# FRAM-DIP.net
KiCad netlist of a schematic drawn in EAGLE
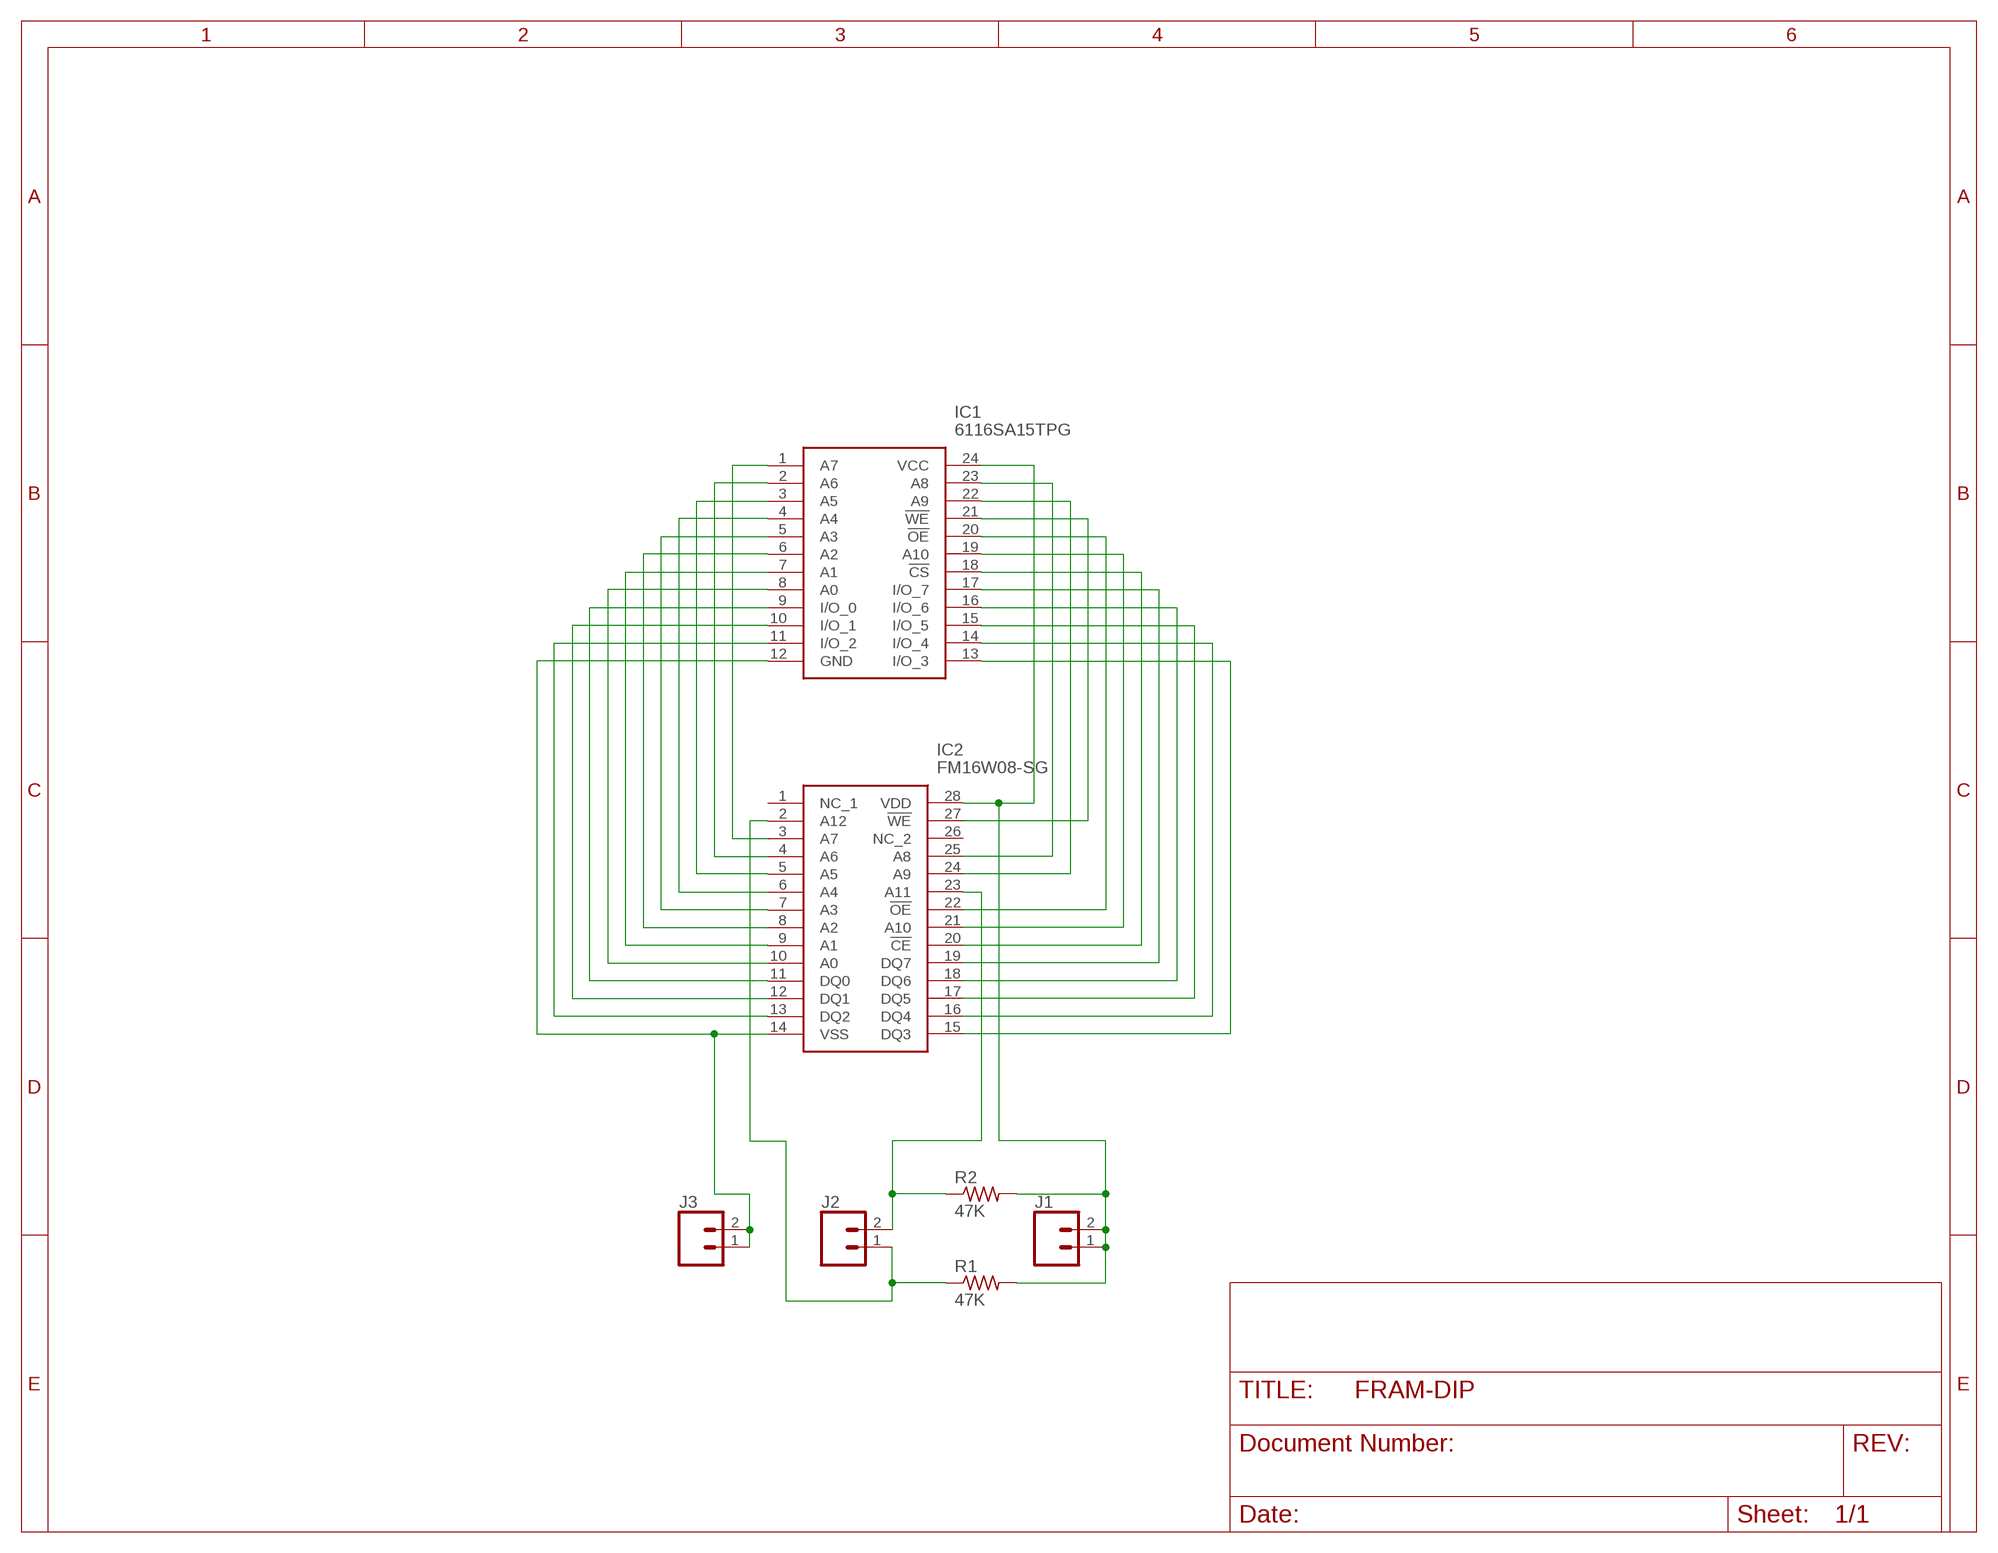
[diagram p0: schematic, sheet 1]

(export (version "E")
  (design (tool "Eeschema 10.0.6"))
  (components
    (comp (ref "IC1")
      (value "6116SA15TPG")
      (footprint "eagle-import:DIP864W51P254L3169H381Q24N")
      (fields (field (name "MOUSER_PART_NUMBER") "972-6116SA15TPG"))
      (libsource (lib "eagle-import") (part "6116SA15TPG"))
    )
    (comp (ref "IC2")
      (value "FM16W08-SG")
      (footprint "eagle-import:SOIC127P1032X267-28N")
      (fields (field (name "MOUSER_PART_NUMBER") "877-FM16W08-SG"))
      (libsource (lib "eagle-import") (part "FM16W08-SG"))
    )
    (comp (ref "J1")
      (value "CONN_02")
      (footprint "eagle-import:1X02")
      (libsource (lib "eagle-import") (part "CONN_02"))
    )
    (comp (ref "J2")
      (value "CONN_02")
      (footprint "eagle-import:1X02")
      (libsource (lib "eagle-import") (part "CONN_02"))
    )
    (comp (ref "J3")
      (value "CONN_02")
      (footprint "eagle-import:1X02")
      (libsource (lib "eagle-import") (part "CONN_02"))
    )
    (comp (ref "R1")
      (value "47K")
      (footprint "eagle-import:R0805")
      (libsource (lib "eagle-import") (part "R-US_R0805"))
    )
    (comp (ref "R2")
      (value "47K")
      (footprint "eagle-import:R0805")
      (libsource (lib "eagle-import") (part "R-US_R0805"))
    )
  )
  (nets
    (net (code "1") (name "Net-(IC1-A0)") (class "Default")
      (node (ref "IC1") (pin "8") (pinfunction "A0_8") (pintype "bidirectional"))
      (node (ref "IC2") (pin "10") (pinfunction "A0_10") (pintype "input"))
    )
    (net (code "2") (name "Net-(IC1-A1)") (class "Default")
      (node (ref "IC1") (pin "7") (pinfunction "A1_7") (pintype "bidirectional"))
      (node (ref "IC2") (pin "9") (pinfunction "A1_9") (pintype "input"))
    )
    (net (code "3") (name "Net-(IC1-A2)") (class "Default")
      (node (ref "IC1") (pin "6") (pinfunction "A2_6") (pintype "bidirectional"))
      (node (ref "IC2") (pin "8") (pinfunction "A2_8") (pintype "input"))
    )
    (net (code "4") (name "Net-(IC1-A3)") (class "Default")
      (node (ref "IC1") (pin "5") (pinfunction "A3_5") (pintype "bidirectional"))
      (node (ref "IC2") (pin "7") (pinfunction "A3_7") (pintype "input"))
    )
    (net (code "5") (name "Net-(IC1-A4)") (class "Default")
      (node (ref "IC1") (pin "4") (pinfunction "A4_4") (pintype "bidirectional"))
      (node (ref "IC2") (pin "6") (pinfunction "A4_6") (pintype "input"))
    )
    (net (code "6") (name "Net-(IC1-A5)") (class "Default")
      (node (ref "IC1") (pin "3") (pinfunction "A5_3") (pintype "bidirectional"))
      (node (ref "IC2") (pin "5") (pinfunction "A5_5") (pintype "input"))
    )
    (net (code "7") (name "Net-(IC1-A6)") (class "Default")
      (node (ref "IC1") (pin "2") (pinfunction "A6_2") (pintype "bidirectional"))
      (node (ref "IC2") (pin "4") (pinfunction "A6_4") (pintype "input"))
    )
    (net (code "8") (name "Net-(IC1-A7)") (class "Default")
      (node (ref "IC1") (pin "1") (pinfunction "A7_1") (pintype "bidirectional"))
      (node (ref "IC2") (pin "3") (pinfunction "A7_3") (pintype "input"))
    )
    (net (code "9") (name "Net-(IC1-A8)") (class "Default")
      (node (ref "IC1") (pin "23") (pinfunction "A8_23") (pintype "bidirectional"))
      (node (ref "IC2") (pin "25") (pinfunction "A8_25") (pintype "input"))
    )
    (net (code "10") (name "Net-(IC1-A9)") (class "Default")
      (node (ref "IC1") (pin "22") (pinfunction "A9_22") (pintype "bidirectional"))
      (node (ref "IC2") (pin "24") (pinfunction "A9_24") (pintype "input"))
    )
    (net (code "11") (name "Net-(IC1-A10)") (class "Default")
      (node (ref "IC1") (pin "19") (pinfunction "A10_19") (pintype "bidirectional"))
      (node (ref "IC2") (pin "21") (pinfunction "A10_21") (pintype "input"))
    )
    (net (code "12") (name "Net-(IC1-GND)") (class "Default")
      (node (ref "IC1") (pin "12") (pinfunction "GND_12") (pintype "bidirectional"))
      (node (ref "IC2") (pin "14") (pinfunction "VSS_14") (pintype "power_in"))
      (node (ref "J3") (pin "1") (pinfunction "1_1") (pintype "passive"))
      (node (ref "J3") (pin "2") (pinfunction "2_2") (pintype "passive"))
    )
    (net (code "13") (name "Net-(IC1-I{slash}O_0)") (class "Default")
      (node (ref "IC1") (pin "9") (pinfunction "I/O_0_9") (pintype "bidirectional"))
      (node (ref "IC2") (pin "11") (pinfunction "DQ0_11") (pintype "bidirectional"))
    )
    (net (code "14") (name "Net-(IC1-I{slash}O_1)") (class "Default")
      (node (ref "IC1") (pin "10") (pinfunction "I/O_1_10") (pintype "bidirectional"))
      (node (ref "IC2") (pin "12") (pinfunction "DQ1_12") (pintype "bidirectional"))
    )
    (net (code "15") (name "Net-(IC1-I{slash}O_2)") (class "Default")
      (node (ref "IC1") (pin "11") (pinfunction "I/O_2_11") (pintype "bidirectional"))
      (node (ref "IC2") (pin "13") (pinfunction "DQ2_13") (pintype "bidirectional"))
    )
    (net (code "16") (name "Net-(IC1-I{slash}O_3)") (class "Default")
      (node (ref "IC1") (pin "13") (pinfunction "I/O_3_13") (pintype "bidirectional"))
      (node (ref "IC2") (pin "15") (pinfunction "DQ3_15") (pintype "bidirectional"))
    )
    (net (code "17") (name "Net-(IC1-I{slash}O_4)") (class "Default")
      (node (ref "IC1") (pin "14") (pinfunction "I/O_4_14") (pintype "bidirectional"))
      (node (ref "IC2") (pin "16") (pinfunction "DQ4_16") (pintype "bidirectional"))
    )
    (net (code "18") (name "Net-(IC1-I{slash}O_5)") (class "Default")
      (node (ref "IC1") (pin "15") (pinfunction "I/O_5_15") (pintype "bidirectional"))
      (node (ref "IC2") (pin "17") (pinfunction "DQ5_17") (pintype "bidirectional"))
    )
    (net (code "19") (name "Net-(IC1-I{slash}O_6)") (class "Default")
      (node (ref "IC1") (pin "16") (pinfunction "I/O_6_16") (pintype "bidirectional"))
      (node (ref "IC2") (pin "18") (pinfunction "DQ6_18") (pintype "bidirectional"))
    )
    (net (code "20") (name "Net-(IC1-I{slash}O_7)") (class "Default")
      (node (ref "IC1") (pin "17") (pinfunction "I/O_7_17") (pintype "bidirectional"))
      (node (ref "IC2") (pin "19") (pinfunction "DQ7_19") (pintype "bidirectional"))
    )
    (net (code "21") (name "Net-(IC1-VCC)") (class "Default")
      (node (ref "IC1") (pin "24") (pinfunction "VCC_24") (pintype "bidirectional"))
      (node (ref "IC2") (pin "28") (pinfunction "VDD_28") (pintype "power_in"))
      (node (ref "J1") (pin "1") (pinfunction "1_1") (pintype "passive"))
      (node (ref "J1") (pin "2") (pinfunction "2_2") (pintype "passive"))
      (node (ref "R1") (pin "2") (pinfunction "2_2") (pintype "passive"))
      (node (ref "R2") (pin "2") (pinfunction "2_2") (pintype "passive"))
    )
    (net (code "22") (name "Net-(IC1-~{CS})") (class "Default")
      (node (ref "IC1") (pin "18") (pinfunction "~{CS}_18") (pintype "bidirectional"))
      (node (ref "IC2") (pin "20") (pinfunction "~{CE}_20") (pintype "input"))
    )
    (net (code "23") (name "Net-(IC1-~{OE})") (class "Default")
      (node (ref "IC1") (pin "20") (pinfunction "~{OE}_20") (pintype "bidirectional"))
      (node (ref "IC2") (pin "22") (pinfunction "~{OE}_22") (pintype "input"))
    )
    (net (code "24") (name "Net-(IC1-~{WE})") (class "Default")
      (node (ref "IC1") (pin "21") (pinfunction "~{WE}_21") (pintype "bidirectional"))
      (node (ref "IC2") (pin "27") (pinfunction "~{WE}_27") (pintype "input"))
    )
    (net (code "25") (name "Net-(IC2-A11)") (class "Default")
      (node (ref "IC2") (pin "23") (pinfunction "A11_23") (pintype "input"))
      (node (ref "J2") (pin "2") (pinfunction "2_2") (pintype "passive"))
      (node (ref "R2") (pin "1") (pinfunction "1_1") (pintype "passive"))
    )
    (net (code "26") (name "Net-(IC2-A12)") (class "Default")
      (node (ref "IC2") (pin "2") (pinfunction "A12_2") (pintype "input"))
      (node (ref "J2") (pin "1") (pinfunction "1_1") (pintype "passive"))
      (node (ref "R1") (pin "1") (pinfunction "1_1") (pintype "passive"))
    )
    (net (code "27") (name "unconnected-(IC2-NC_1-Pad1)") (class "Default")
      (node (ref "IC2") (pin "1") (pinfunction "NC_1_1") (pintype "bidirectional"))
    )
    (net (code "28") (name "unconnected-(IC2-NC_2-Pad26)") (class "Default")
      (node (ref "IC2") (pin "26") (pinfunction "NC_2_26") (pintype "bidirectional"))
    )
  )
)
